# ESP8266_IR_PZEM.net
KiCad netlist of a schematic drawn in Altium Designer
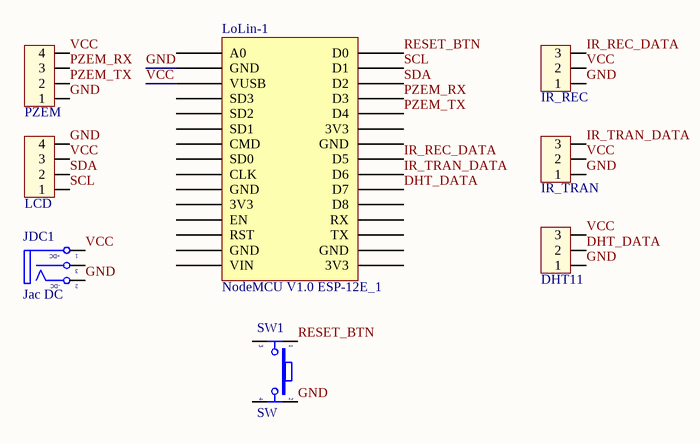
[diagram p0: ESP8266_IR_PZEM.SchDoc]

(export (version "E")
  (design (tool "Eeschema 10.0.6"))
  (components
    (comp (ref "JDC1")
      (value "Jac DC")
      (footprint "DC-IN")
      (description "Jac DC input")
      (libsource (lib "Library AL") (part "DCIN"))
    )
    (comp (ref "JP1")
      (value "LCD")
      (footprint "CON4")
      (description "Connector 4")
      (libsource (lib "Library AL") (part "Con4"))
    )
    (comp (ref "JP2")
      (value "IR_REC")
      (footprint "CON3")
      (description "Connector 3")
      (libsource (lib "Library AL") (part "Con3"))
    )
    (comp (ref "JP3")
      (value "IR_TRAN")
      (footprint "CON3")
      (description "Connector 3")
      (libsource (lib "Library AL") (part "Con3"))
    )
    (comp (ref "JP4")
      (value "DHT11")
      (footprint "CON3")
      (description "Connector 3")
      (libsource (lib "Library AL") (part "Con3"))
    )
    (comp (ref "JP5")
      (value "PZEM")
      (footprint "CON4")
      (description "Connector 4")
      (libsource (lib "Library AL") (part "Con4"))
    )
    (comp (ref "LoLin-1")
      (value "NodeMCU V1.0 ESP-12E_1")
      (footprint "LoLin NodeMcu V3")
      (description "LoLin NodeMCU V3")
      (libsource (lib "nodemcu") (part "NodeMCU V1.0 ESP-12E_1"))
    )
    (comp (ref "SW1")
      (value "SW")
      (footprint "SW4")
      (description "Switch button 4 pin")
      (libsource (lib "Library AL") (part "SW4"))
    )
  )
  (nets
    (net (code "1") (name "/DHT_DATA") (class "Default")
      (node (ref "JP4") (pin "2") (pinfunction "2_2") (pintype "passive"))
      (node (ref "LoLin-1") (pin "D7") (pinfunction "D7_D7") (pintype "passive"))
    )
    (net (code "2") (name "/GND") (class "Default")
      (node (ref "JDC1") (pin "2") (pinfunction "TN_2") (pintype "passive"))
      (node (ref "JP1") (pin "4") (pinfunction "4_4") (pintype "passive"))
      (node (ref "JP2") (pin "1") (pinfunction "1_1") (pintype "passive"))
      (node (ref "JP3") (pin "1") (pinfunction "1_1") (pintype "passive"))
      (node (ref "JP4") (pin "1") (pinfunction "1_1") (pintype "passive"))
      (node (ref "JP5") (pin "1") (pinfunction "1_1") (pintype "passive"))
      (node (ref "LoLin-1") (pin "GND") (pinfunction "GND_GND") (pintype "passive"))
      (node (ref "SW1") (pin "2") (pinfunction "2_2") (pintype "passive"))
    )
    (net (code "3") (name "/IR_REC_DATA") (class "Default")
      (node (ref "JP2") (pin "3") (pinfunction "3_3") (pintype "passive"))
      (node (ref "LoLin-1") (pin "D5") (pinfunction "D5_D5") (pintype "passive"))
    )
    (net (code "4") (name "/IR_TRAN_DATA") (class "Default")
      (node (ref "JP3") (pin "3") (pinfunction "3_3") (pintype "passive"))
      (node (ref "LoLin-1") (pin "D6") (pinfunction "D6_D6") (pintype "passive"))
    )
    (net (code "5") (name "/PZEM_RX") (class "Default")
      (node (ref "JP5") (pin "3") (pinfunction "3_3") (pintype "passive"))
      (node (ref "LoLin-1") (pin "D3") (pinfunction "D3_D3") (pintype "passive"))
    )
    (net (code "6") (name "/PZEM_TX") (class "Default")
      (node (ref "JP5") (pin "2") (pinfunction "2_2") (pintype "passive"))
      (node (ref "LoLin-1") (pin "D4") (pinfunction "D4_D4") (pintype "passive"))
    )
    (net (code "7") (name "/RESET_BTN") (class "Default")
      (node (ref "LoLin-1") (pin "D0") (pinfunction "D0_D0") (pintype "passive"))
      (node (ref "SW1") (pin "1") (pinfunction "1_1") (pintype "passive"))
    )
    (net (code "8") (name "/SCL") (class "Default")
      (node (ref "JP1") (pin "1") (pinfunction "1_1") (pintype "passive"))
      (node (ref "LoLin-1") (pin "D1") (pinfunction "D1_D1") (pintype "passive"))
    )
    (net (code "9") (name "/SDA") (class "Default")
      (node (ref "JP1") (pin "2") (pinfunction "2_2") (pintype "passive"))
      (node (ref "LoLin-1") (pin "D2") (pinfunction "D2_D2") (pintype "passive"))
    )
    (net (code "10") (name "/VCC") (class "Default")
      (node (ref "JDC1") (pin "1") (pinfunction "T_1") (pintype "passive"))
      (node (ref "JP1") (pin "3") (pinfunction "3_3") (pintype "passive"))
      (node (ref "JP2") (pin "2") (pinfunction "2_2") (pintype "passive"))
      (node (ref "JP3") (pin "2") (pinfunction "2_2") (pintype "passive"))
      (node (ref "JP4") (pin "3") (pinfunction "3_3") (pintype "passive"))
      (node (ref "JP5") (pin "4") (pinfunction "4_4") (pintype "passive"))
      (node (ref "LoLin-1") (pin "VUSB") (pinfunction "VUSB_VUSB") (pintype "passive"))
    )
    (net (code "11") (name "unconnected-(JDC1-S-Pad3)") (class "Default")
      (node (ref "JDC1") (pin "3") (pinfunction "S_3") (pintype "power_in"))
    )
    (net (code "12") (name "unconnected-(LoLin-1-Pad3V3)") (class "Default")
      (node (ref "LoLin-1") (pin "3V3") (pinfunction "3V3_3V3") (pintype "passive"))
    )
    (net (code "13") (name "unconnected-(LoLin-1-Pad3V3)_1") (class "Default")
      (node (ref "LoLin-1") (pin "3V3") (pinfunction "3V3_3V3") (pintype "passive"))
    )
    (net (code "14") (name "unconnected-(LoLin-1-Pad3V3)_2") (class "Default")
      (node (ref "LoLin-1") (pin "3V3") (pinfunction "3V3_3V3") (pintype "passive"))
    )
    (net (code "15") (name "unconnected-(LoLin-1-PadA0)") (class "Default")
      (node (ref "LoLin-1") (pin "A0") (pinfunction "A0_A0") (pintype "passive"))
    )
    (net (code "16") (name "unconnected-(LoLin-1-PadCLK)") (class "Default")
      (node (ref "LoLin-1") (pin "CLK") (pinfunction "CLK_CLK") (pintype "passive"))
    )
    (net (code "17") (name "unconnected-(LoLin-1-PadCMD)") (class "Default")
      (node (ref "LoLin-1") (pin "CMD") (pinfunction "CMD_CMD") (pintype "passive"))
    )
    (net (code "18") (name "unconnected-(LoLin-1-PadD8)") (class "Default")
      (node (ref "LoLin-1") (pin "D8") (pinfunction "D8_D8") (pintype "passive"))
    )
    (net (code "19") (name "unconnected-(LoLin-1-PadEN)") (class "Default")
      (node (ref "LoLin-1") (pin "EN") (pinfunction "EN_EN") (pintype "passive"))
    )
    (net (code "20") (name "unconnected-(LoLin-1-PadGND)") (class "Default")
      (node (ref "LoLin-1") (pin "GND") (pinfunction "GND_GND") (pintype "passive"))
    )
    (net (code "21") (name "unconnected-(LoLin-1-PadGND)_1") (class "Default")
      (node (ref "LoLin-1") (pin "GND") (pinfunction "GND_GND") (pintype "passive"))
    )
    (net (code "22") (name "unconnected-(LoLin-1-PadGND)_2") (class "Default")
      (node (ref "LoLin-1") (pin "GND") (pinfunction "GND_GND") (pintype "passive"))
    )
    (net (code "23") (name "unconnected-(LoLin-1-PadGND)_3") (class "Default")
      (node (ref "LoLin-1") (pin "GND") (pinfunction "GND_GND") (pintype "passive"))
    )
    (net (code "24") (name "unconnected-(LoLin-1-PadRST)") (class "Default")
      (node (ref "LoLin-1") (pin "RST") (pinfunction "RST_RST") (pintype "passive"))
    )
    (net (code "25") (name "unconnected-(LoLin-1-PadRX)") (class "Default")
      (node (ref "LoLin-1") (pin "RX") (pinfunction "RX_RX") (pintype "passive"))
    )
    (net (code "26") (name "unconnected-(LoLin-1-PadSD0)") (class "Default")
      (node (ref "LoLin-1") (pin "SD0") (pinfunction "SD0_SD0") (pintype "passive"))
    )
    (net (code "27") (name "unconnected-(LoLin-1-PadSD1)") (class "Default")
      (node (ref "LoLin-1") (pin "SD1") (pinfunction "SD1_SD1") (pintype "passive"))
    )
    (net (code "28") (name "unconnected-(LoLin-1-PadSD2)") (class "Default")
      (node (ref "LoLin-1") (pin "SD2") (pinfunction "SD2_SD2") (pintype "passive"))
    )
    (net (code "29") (name "unconnected-(LoLin-1-PadSD3)") (class "Default")
      (node (ref "LoLin-1") (pin "SD3") (pinfunction "SD3_SD3") (pintype "passive"))
    )
    (net (code "30") (name "unconnected-(LoLin-1-PadTX)") (class "Default")
      (node (ref "LoLin-1") (pin "TX") (pinfunction "TX_TX") (pintype "passive"))
    )
    (net (code "31") (name "unconnected-(LoLin-1-PadVIN)") (class "Default")
      (node (ref "LoLin-1") (pin "VIN") (pinfunction "VIN_VIN") (pintype "passive"))
    )
    (net (code "32") (name "unconnected-(SW1-Pad3)") (class "Default")
      (node (ref "SW1") (pin "3") (pinfunction "3_3") (pintype "passive"))
    )
    (net (code "33") (name "unconnected-(SW1-Pad4)") (class "Default")
      (node (ref "SW1") (pin "4") (pinfunction "4_4") (pintype "passive"))
    )
  )
)
